# uszko.net
KiCad netlist of a schematic drawn in EAGLE
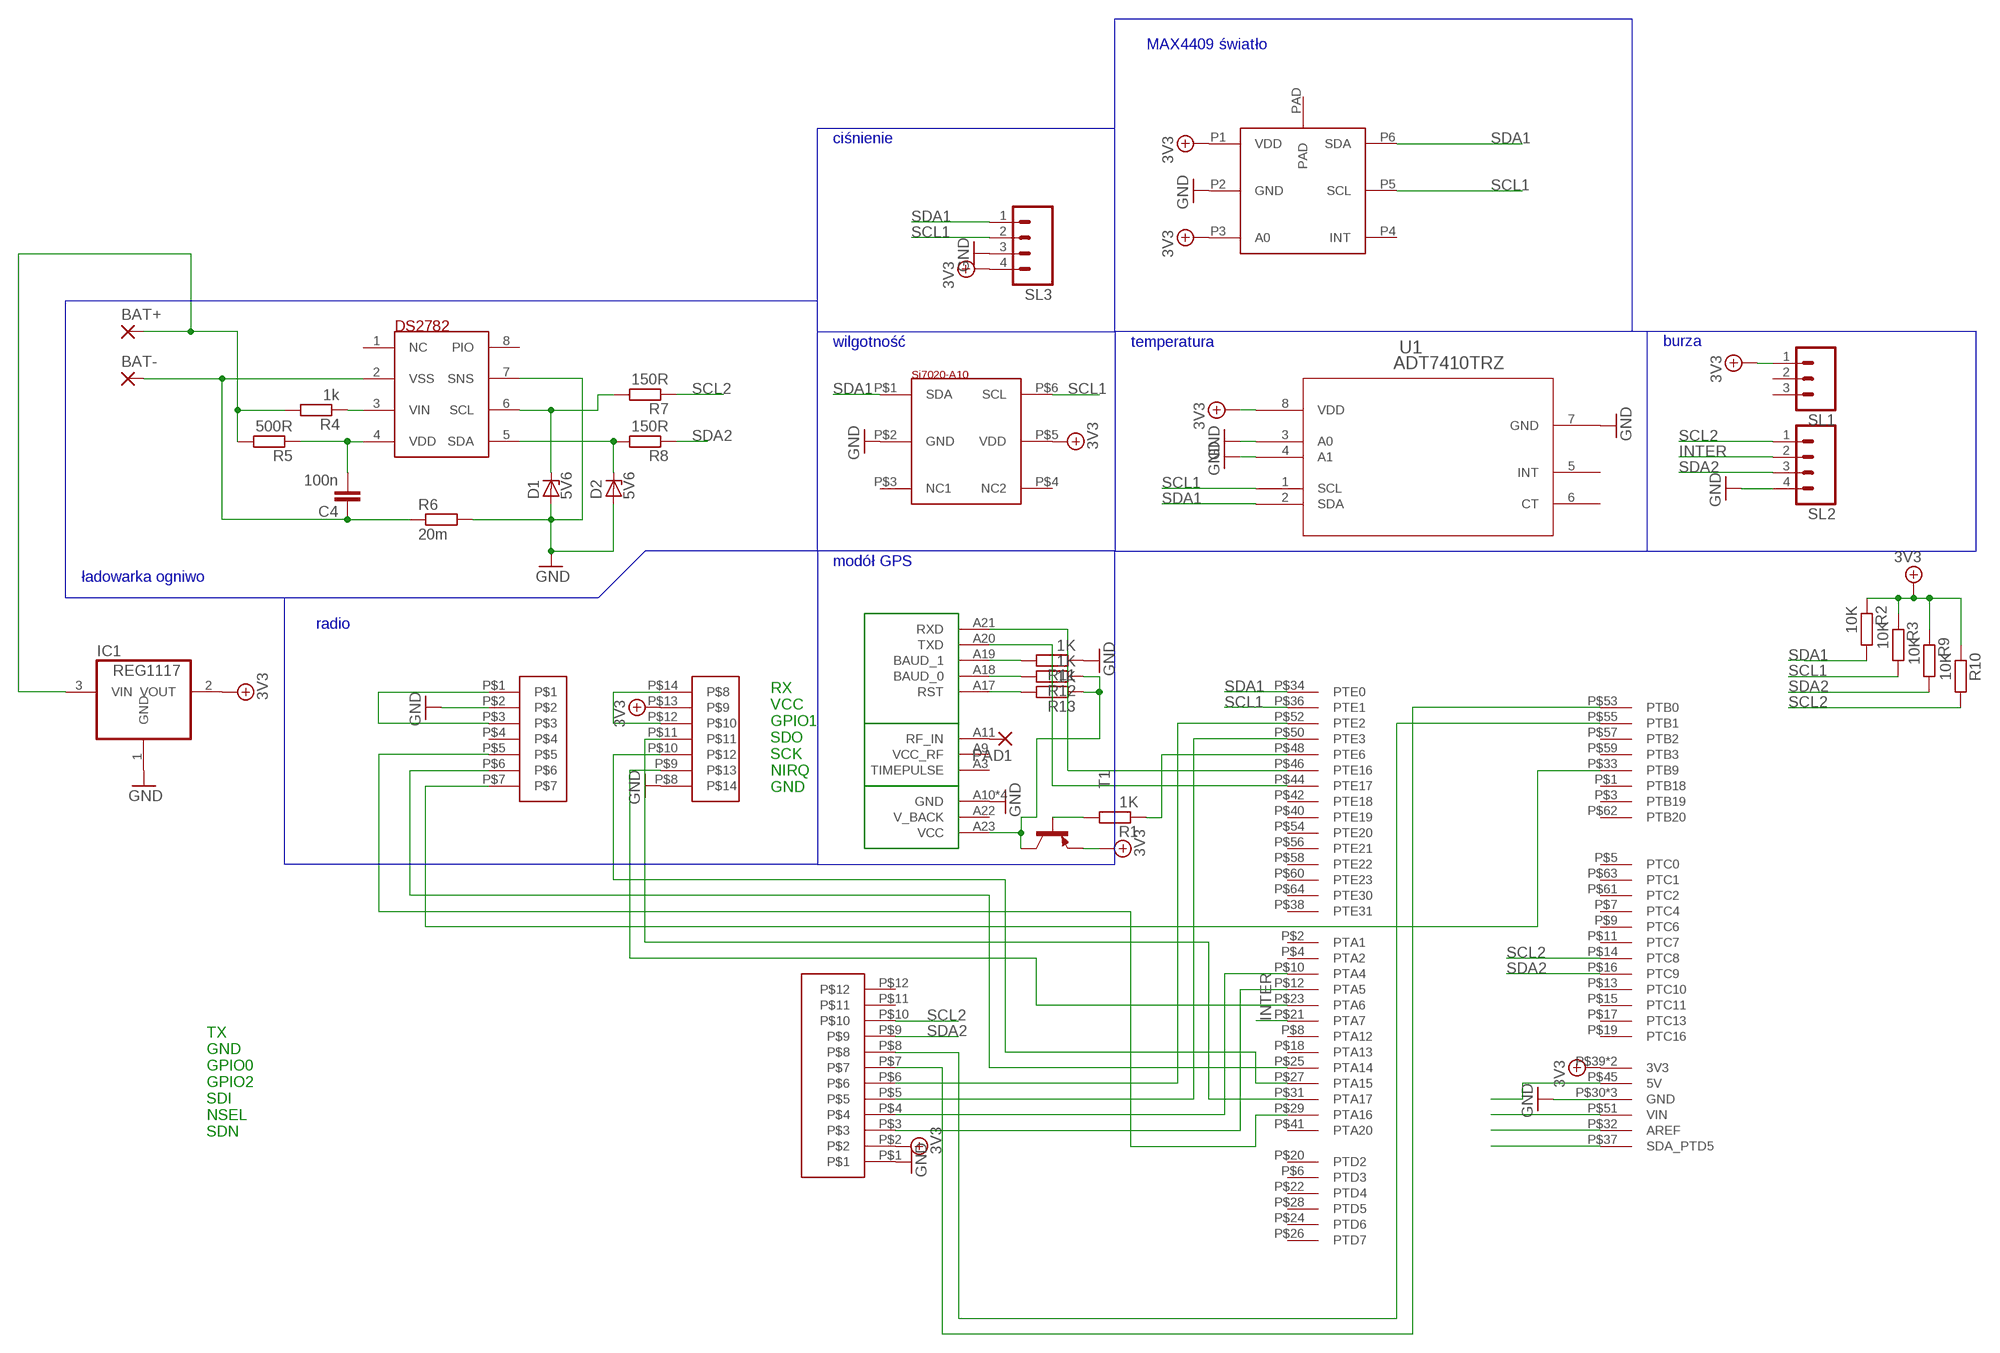
[diagram p0: schematic, sheet 1]

(export (version "E")
  (design (tool "Eeschema 10.0.6"))
  (components
    (comp (ref "BAT+")
      (value "2,54/0,8")
      (footprint "eagle-import:2,54_0,8")
      (libsource (lib "eagle-import") (part "2,54/0,8"))
    )
    (comp (ref "BAT-")
      (value "2,54/0,8")
      (footprint "eagle-import:2,54_0,8")
      (libsource (lib "eagle-import") (part "2,54/0,8"))
    )
    (comp (ref "C4")
      (value "100n")
      (footprint "eagle-import:C0805")
      (libsource (lib "eagle-import") (part "C-EUC0805"))
    )
    (comp (ref "D1")
      (value "5V6")
      (footprint "eagle-import:SOD80C")
      (libsource (lib "eagle-import") (part "ZENER-DIODESOD80C"))
    )
    (comp (ref "D2")
      (value "5V6")
      (footprint "eagle-import:SOD80C")
      (libsource (lib "eagle-import") (part "ZENER-DIODESOD80C"))
    )
    (comp (ref "IC1")
      (value "REG1117")
      (footprint "eagle-import:SOT223")
      (libsource (lib "eagle-import") (part "REG1117"))
    )
    (comp (ref "PAD1")
      (value "2,15/1,0")
      (footprint "eagle-import:2,15_1,0")
      (libsource (lib "eagle-import") (part "2,15/1,0"))
    )
    (comp (ref "R1")
      (value "1K")
      (footprint "eagle-import:M0805")
      (libsource (lib "eagle-import") (part "R-EU_M0805"))
    )
    (comp (ref "R2")
      (value "10K")
      (footprint "eagle-import:M0805")
      (libsource (lib "eagle-import") (part "R-EU_M0805"))
    )
    (comp (ref "R3")
      (value "10K")
      (footprint "eagle-import:M0805")
      (libsource (lib "eagle-import") (part "R-EU_M0805"))
    )
    (comp (ref "R4")
      (value "1k")
      (footprint "eagle-import:M0805")
      (libsource (lib "eagle-import") (part "R-EU_M0805"))
    )
    (comp (ref "R5")
      (value "500R")
      (footprint "eagle-import:M0805")
      (libsource (lib "eagle-import") (part "R-EU_M0805"))
    )
    (comp (ref "R6")
      (value "20m")
      (footprint "eagle-import:M1206")
      (libsource (lib "eagle-import") (part "R-EU_M1206"))
    )
    (comp (ref "R7")
      (value "150R")
      (footprint "eagle-import:M0805")
      (libsource (lib "eagle-import") (part "R-EU_M0805"))
    )
    (comp (ref "R8")
      (value "150R")
      (footprint "eagle-import:M0805")
      (libsource (lib "eagle-import") (part "R-EU_M0805"))
    )
    (comp (ref "R9")
      (value "10K")
      (footprint "eagle-import:M0805")
      (libsource (lib "eagle-import") (part "R-EU_M0805"))
    )
    (comp (ref "R10")
      (value "10K")
      (footprint "eagle-import:M0805")
      (libsource (lib "eagle-import") (part "R-EU_M0805"))
    )
    (comp (ref "R11")
      (value "1K")
      (footprint "eagle-import:M0805")
      (libsource (lib "eagle-import") (part "R-EU_M0805"))
    )
    (comp (ref "R12")
      (value "1K")
      (footprint "eagle-import:M0805")
      (libsource (lib "eagle-import") (part "R-EU_M0805"))
    )
    (comp (ref "R13")
      (value "1K")
      (footprint "eagle-import:M0805")
      (libsource (lib "eagle-import") (part "R-EU_M0805"))
    )
    (comp (ref "SL1")
      (value "M03")
      (footprint "eagle-import:03P")
      (libsource (lib "eagle-import") (part "M03"))
    )
    (comp (ref "SL2")
      (value "M04")
      (footprint "eagle-import:04P")
      (libsource (lib "eagle-import") (part "M04"))
    )
    (comp (ref "SL3")
      (value "M04")
      (footprint "eagle-import:04P")
      (fields (field (name "OC_FARNELL") "unknown") (field (name "OC_NEWARK") "unknown"))
      (libsource (lib "eagle-import") (part "M04"))
    )
    (comp (ref "T1")
      (value "-PNP-SOT23-BCE")
      (footprint "eagle-import:SOT23-BCE")
      (libsource (lib "eagle-import") (part "-PNP-SOT23-BCE"))
    )
    (comp (ref "U$1")
      (value "INTO_CON")
      (footprint "eagle-import:INTO_CON")
      (libsource (lib "eagle-import") (part "INTO_CON"))
    )
    (comp (ref "U$2")
      (value "GTS-4E-60")
      (footprint "eagle-import:GTS-4E-60")
      (libsource (lib "eagle-import") (part "GTS-4E-60"))
    )
    (comp (ref "U$3")
      (value "2X7PIN")
      (footprint "eagle-import:2X7PINCON")
      (libsource (lib "eagle-import") (part "2X7PIN"))
    )
    (comp (ref "U$4")
      (value "SI7020-A10")
      (footprint "eagle-import:DFN6(3X3MM)")
      (libsource (lib "eagle-import") (part "SI7020-A10"))
    )
    (comp (ref "U$5")
      (value "12PINCON")
      (footprint "eagle-import:12PIN2MMCON")
      (libsource (lib "eagle-import") (part "12PINCON"))
    )
    (comp (ref "U$6")
      (value "MAX44006")
      (footprint "eagle-import:6OTDFN")
      (libsource (lib "eagle-import") (part "MAX44006"))
    )
    (comp (ref "U$7")
      (value "DS2782")
      (footprint "eagle-import:TSSOP8")
      (libsource (lib "eagle-import") (part "DS2782"))
    )
    (comp (ref "U1")
      (value "ADT7410TRZ")
      (footprint "eagle-import:R_8")
      (libsource (lib "eagle-import") (part "ADT7410TRZ"))
    )
  )
  (nets
    (net (code "1") (name "/INTER") (class "Default")
      (node (ref "SL2") (pin "2") (pinfunction "2_2") (pintype "passive"))
      (node (ref "U$1") (pin "P$21") (pinfunction "PTA7_P$21") (pintype "bidirectional"))
    )
    (net (code "2") (name "/SCL1") (class "Default")
      (node (ref "R3") (pin "2") (pinfunction "2_2") (pintype "passive"))
      (node (ref "SL3") (pin "2") (pinfunction "2_2") (pintype "passive"))
      (node (ref "U$1") (pin "P$36") (pinfunction "PTE1_P$36") (pintype "bidirectional"))
      (node (ref "U$4") (pin "P$6") (pinfunction "SCL_P$6") (pintype "bidirectional"))
      (node (ref "U$6") (pin "P5") (pinfunction "SCL_P5") (pintype "bidirectional"))
      (node (ref "U1") (pin "1") (pinfunction "SCL_1") (pintype "passive"))
    )
    (net (code "3") (name "/SCL2") (class "Default")
      (node (ref "R10") (pin "2") (pinfunction "2_2") (pintype "passive"))
      (node (ref "R7") (pin "1") (pinfunction "1_1") (pintype "passive"))
      (node (ref "SL2") (pin "1") (pinfunction "1_1") (pintype "passive"))
      (node (ref "U$1") (pin "P$14") (pinfunction "PTC8_P$14") (pintype "bidirectional"))
      (node (ref "U$5") (pin "P$10") (pinfunction "P$10_P$10") (pintype "bidirectional"))
    )
    (net (code "4") (name "/SDA1") (class "Default")
      (node (ref "R2") (pin "2") (pinfunction "2_2") (pintype "passive"))
      (node (ref "SL3") (pin "1") (pinfunction "1_1") (pintype "passive"))
      (node (ref "U$1") (pin "P$34") (pinfunction "PTE0_P$34") (pintype "bidirectional"))
      (node (ref "U$4") (pin "P$1") (pinfunction "SDA_P$1") (pintype "bidirectional"))
      (node (ref "U$6") (pin "P6") (pinfunction "SDA_P6") (pintype "bidirectional"))
      (node (ref "U1") (pin "2") (pinfunction "SDA_2") (pintype "passive"))
    )
    (net (code "5") (name "/SDA2") (class "Default")
      (node (ref "R8") (pin "1") (pinfunction "1_1") (pintype "passive"))
      (node (ref "R9") (pin "2") (pinfunction "2_2") (pintype "passive"))
      (node (ref "SL2") (pin "3") (pinfunction "3_3") (pintype "passive"))
      (node (ref "U$1") (pin "P$16") (pinfunction "PTC9_P$16") (pintype "bidirectional"))
      (node (ref "U$5") (pin "P$9") (pinfunction "P$9_P$9") (pintype "bidirectional"))
    )
    (net (code "6") (name "3V3") (class "Default")
      (node (ref "IC1") (pin "2") (pinfunction "VOUT_2") (pintype "output"))
      (node (ref "R10") (pin "1") (pinfunction "1_1") (pintype "passive"))
      (node (ref "R2") (pin "1") (pinfunction "1_1") (pintype "passive"))
      (node (ref "R3") (pin "1") (pinfunction "1_1") (pintype "passive"))
      (node (ref "R9") (pin "1") (pinfunction "1_1") (pintype "passive"))
      (node (ref "SL1") (pin "1") (pinfunction "1_1") (pintype "passive"))
      (node (ref "SL3") (pin "4") (pinfunction "4_4") (pintype "passive"))
      (node (ref "T1") (pin "E") (pinfunction "E_E") (pintype "passive"))
      (node (ref "U$1") (pin "P$39") (pinfunction "3V3_P$39") (pintype "bidirectional"))
      (node (ref "U$1") (pin "P$43") (pinfunction "3V3_P$43") (pintype "bidirectional"))
      (node (ref "U$3") (pin "P$13") (pinfunction "P$9_P$13") (pintype "bidirectional"))
      (node (ref "U$4") (pin "P$5") (pinfunction "VDD_P$5") (pintype "bidirectional"))
      (node (ref "U$5") (pin "P$2") (pinfunction "P$2_P$2") (pintype "bidirectional"))
      (node (ref "U$6") (pin "P1") (pinfunction "VDD_P1") (pintype "bidirectional"))
      (node (ref "U$6") (pin "P3") (pinfunction "A0_P3") (pintype "bidirectional"))
      (node (ref "U1") (pin "8") (pinfunction "VDD_8") (pintype "passive"))
    )
    (net (code "7") (name "GND") (class "Default")
      (node (ref "D1") (pin "A") (pinfunction "A_A") (pintype "passive"))
      (node (ref "D2") (pin "A") (pinfunction "A_A") (pintype "passive"))
      (node (ref "IC1") (pin "1") (pinfunction "GND_1") (pintype "power_in"))
      (node (ref "R11") (pin "1") (pinfunction "1_1") (pintype "passive"))
      (node (ref "R6") (pin "2") (pinfunction "2_2") (pintype "passive"))
      (node (ref "SL2") (pin "4") (pinfunction "4_4") (pintype "passive"))
      (node (ref "SL3") (pin "3") (pinfunction "3_3") (pintype "passive"))
      (node (ref "U$1") (pin "P$30") (pinfunction "GND_P$30") (pintype "bidirectional"))
      (node (ref "U$1") (pin "P$47") (pinfunction "GND_P$47") (pintype "bidirectional"))
      (node (ref "U$1") (pin "P$49") (pinfunction "GND_P$49") (pintype "bidirectional"))
      (node (ref "U$2") (pin "A10") (pinfunction "GND_A10") (pintype "bidirectional"))
      (node (ref "U$2") (pin "A12") (pinfunction "GND_A12") (pintype "bidirectional"))
      (node (ref "U$2") (pin "A13") (pinfunction "GND_A13") (pintype "bidirectional"))
      (node (ref "U$2") (pin "A24") (pinfunction "GND_A24") (pintype "bidirectional"))
      (node (ref "U$3") (pin "P$2") (pinfunction "P$2_P$2") (pintype "bidirectional"))
      (node (ref "U$3") (pin "P$8") (pinfunction "P$14_P$8") (pintype "bidirectional"))
      (node (ref "U$4") (pin "P$2") (pinfunction "GND_P$2") (pintype "bidirectional"))
      (node (ref "U$5") (pin "P$1") (pinfunction "P$1_P$1") (pintype "bidirectional"))
      (node (ref "U$6") (pin "P2") (pinfunction "GND_P2") (pintype "bidirectional"))
      (node (ref "U$7") (pin "7") (pinfunction "SNS_7") (pintype "bidirectional"))
      (node (ref "U1") (pin "3") (pinfunction "A0_3") (pintype "passive"))
      (node (ref "U1") (pin "4") (pinfunction "A1_4") (pintype "passive"))
      (node (ref "U1") (pin "7") (pinfunction "GND_7") (pintype "passive"))
    )
    (net (code "8") (name "Net-(BAT+-P)") (class "Default")
      (node (ref "BAT+") (pin "1") (pinfunction "P_1") (pintype "passive"))
      (node (ref "IC1") (pin "3") (pinfunction "VIN_3") (pintype "input"))
      (node (ref "R4") (pin "2") (pinfunction "2_2") (pintype "passive"))
      (node (ref "R5") (pin "2") (pinfunction "2_2") (pintype "passive"))
    )
    (net (code "9") (name "Net-(BAT--P)") (class "Default")
      (node (ref "BAT-") (pin "1") (pinfunction "P_1") (pintype "passive"))
      (node (ref "C4") (pin "1") (pinfunction "1_1") (pintype "passive"))
      (node (ref "R6") (pin "1") (pinfunction "1_1") (pintype "passive"))
      (node (ref "U$7") (pin "2") (pinfunction "VSS_2") (pintype "bidirectional"))
    )
    (net (code "10") (name "Net-(PAD1-P)") (class "Default")
      (node (ref "PAD1") (pin "1") (pinfunction "P_1") (pintype "passive"))
      (node (ref "U$2") (pin "A11") (pinfunction "RF_IN_A11") (pintype "bidirectional"))
    )
    (net (code "11") (name "Net-(R1-Pad2)") (class "Default")
      (node (ref "R1") (pin "2") (pinfunction "2_2") (pintype "passive"))
      (node (ref "T1") (pin "B") (pinfunction "B_B") (pintype "passive"))
    )
    (net (code "12") (name "Net-(U$1-PTA4)") (class "Default")
      (node (ref "U$1") (pin "P$10") (pinfunction "PTA4_P$10") (pintype "bidirectional"))
      (node (ref "U$5") (pin "P$4") (pinfunction "P$4_P$4") (pintype "bidirectional"))
    )
    (net (code "13") (name "Net-(U$1-PTA5)") (class "Default")
      (node (ref "U$1") (pin "P$12") (pinfunction "PTA5_P$12") (pintype "bidirectional"))
      (node (ref "U$5") (pin "P$3") (pinfunction "P$3_P$3") (pintype "bidirectional"))
    )
    (net (code "14") (name "Net-(U$1-PTA6)") (class "Default")
      (node (ref "U$1") (pin "P$23") (pinfunction "PTA6_P$23") (pintype "bidirectional"))
      (node (ref "U$3") (pin "P$9") (pinfunction "P$13_P$9") (pintype "bidirectional"))
    )
    (net (code "15") (name "Net-(U$1-PTA14)") (class "Default")
      (node (ref "U$1") (pin "P$25") (pinfunction "PTA14_P$25") (pintype "bidirectional"))
      (node (ref "U$3") (pin "P$6") (pinfunction "P$6_P$6") (pintype "bidirectional"))
    )
    (net (code "16") (name "Net-(U$1-PTA15)") (class "Default")
      (node (ref "U$1") (pin "P$27") (pinfunction "PTA15_P$27") (pintype "bidirectional"))
      (node (ref "U$3") (pin "P$10") (pinfunction "P$12_P$10") (pintype "bidirectional"))
    )
    (net (code "17") (name "Net-(U$1-PTA16)") (class "Default")
      (node (ref "U$1") (pin "P$29") (pinfunction "PTA16_P$29") (pintype "bidirectional"))
      (node (ref "U$3") (pin "P$5") (pinfunction "P$5_P$5") (pintype "bidirectional"))
    )
    (net (code "18") (name "Net-(U$1-PTA17)") (class "Default")
      (node (ref "U$1") (pin "P$31") (pinfunction "PTA17_P$31") (pintype "bidirectional"))
      (node (ref "U$3") (pin "P$11") (pinfunction "P$11_P$11") (pintype "bidirectional"))
    )
    (net (code "19") (name "Net-(U$1-PTB0)") (class "Default")
      (node (ref "U$1") (pin "P$53") (pinfunction "PTB0_P$53") (pintype "bidirectional"))
      (node (ref "U$5") (pin "P$7") (pinfunction "P$7_P$7") (pintype "bidirectional"))
    )
    (net (code "20") (name "Net-(U$1-PTB1)") (class "Default")
      (node (ref "U$1") (pin "P$55") (pinfunction "PTB1_P$55") (pintype "bidirectional"))
      (node (ref "U$5") (pin "P$8") (pinfunction "P$8_P$8") (pintype "bidirectional"))
    )
    (net (code "21") (name "Net-(U$1-PTB9)") (class "Default")
      (node (ref "U$1") (pin "P$33") (pinfunction "PTB9_P$33") (pintype "bidirectional"))
      (node (ref "U$3") (pin "P$7") (pinfunction "P$7_P$7") (pintype "bidirectional"))
    )
    (net (code "22") (name "Net-(U$1-PTE2)") (class "Default")
      (node (ref "U$1") (pin "P$52") (pinfunction "PTE2_P$52") (pintype "bidirectional"))
      (node (ref "U$5") (pin "P$6") (pinfunction "P$6_P$6") (pintype "bidirectional"))
    )
    (net (code "23") (name "Net-(U$1-PTE3)") (class "Default")
      (node (ref "U$1") (pin "P$50") (pinfunction "PTE3_P$50") (pintype "bidirectional"))
      (node (ref "U$5") (pin "P$5") (pinfunction "P$5_P$5") (pintype "bidirectional"))
    )
    (net (code "24") (name "Net-(U$1-PTE6)") (class "Default")
      (node (ref "R1") (pin "1") (pinfunction "1_1") (pintype "passive"))
      (node (ref "U$1") (pin "P$48") (pinfunction "PTE6_P$48") (pintype "bidirectional"))
    )
    (net (code "25") (name "Net-(U$1-PTE16)") (class "Default")
      (node (ref "U$1") (pin "P$46") (pinfunction "PTE16_P$46") (pintype "bidirectional"))
      (node (ref "U$2") (pin "A21") (pinfunction "RXD_A21") (pintype "bidirectional"))
    )
    (net (code "26") (name "Net-(U$1-PTE17)") (class "Default")
      (node (ref "U$1") (pin "P$44") (pinfunction "PTE17_P$44") (pintype "bidirectional"))
      (node (ref "U$2") (pin "A20") (pinfunction "TXD_A20") (pintype "bidirectional"))
    )
    (net (code "27") (name "Net-(U$2-BAUD_0)") (class "Default")
      (node (ref "R12") (pin "2") (pinfunction "2_2") (pintype "passive"))
      (node (ref "U$2") (pin "A18") (pinfunction "BAUD_0_A18") (pintype "bidirectional"))
    )
    (net (code "28") (name "Net-(U$2-BAUD_1)") (class "Default")
      (node (ref "R11") (pin "2") (pinfunction "2_2") (pintype "passive"))
      (node (ref "U$2") (pin "A19") (pinfunction "BAUD_1_A19") (pintype "bidirectional"))
    )
    (net (code "29") (name "Net-(U$2-RST)") (class "Default")
      (node (ref "R13") (pin "2") (pinfunction "2_2") (pintype "passive"))
      (node (ref "U$2") (pin "A17") (pinfunction "RST_A17") (pintype "bidirectional"))
    )
    (net (code "30") (name "Net-(U$2-VCC)") (class "Default")
      (node (ref "R12") (pin "1") (pinfunction "1_1") (pintype "passive"))
      (node (ref "R13") (pin "1") (pinfunction "1_1") (pintype "passive"))
      (node (ref "T1") (pin "C") (pinfunction "C_C") (pintype "passive"))
      (node (ref "U$2") (pin "A23") (pinfunction "VCC_A23") (pintype "bidirectional"))
    )
    (net (code "31") (name "Net-(U$3-P$10)") (class "Default")
      (node (ref "U$3") (pin "P$12") (pinfunction "P$10_P$12") (pintype "bidirectional"))
      (node (ref "U$3") (pin "P$14") (pinfunction "P$8_P$14") (pintype "bidirectional"))
    )
    (net (code "32") (name "Net-(U$3-PadP$1)") (class "Default")
      (node (ref "U$3") (pin "P$1") (pinfunction "P$1_P$1") (pintype "bidirectional"))
      (node (ref "U$3") (pin "P$3") (pinfunction "P$3_P$3") (pintype "bidirectional"))
    )
    (net (code "33") (name "Net-(U$7-SCL)") (class "Default")
      (node (ref "D1") (pin "C") (pinfunction "C_C") (pintype "passive"))
      (node (ref "R7") (pin "2") (pinfunction "2_2") (pintype "passive"))
      (node (ref "U$7") (pin "6") (pinfunction "SCL_6") (pintype "bidirectional"))
    )
    (net (code "34") (name "Net-(U$7-SDA)") (class "Default")
      (node (ref "D2") (pin "C") (pinfunction "C_C") (pintype "passive"))
      (node (ref "R8") (pin "2") (pinfunction "2_2") (pintype "passive"))
      (node (ref "U$7") (pin "5") (pinfunction "SDA_5") (pintype "bidirectional"))
    )
    (net (code "35") (name "Net-(U$7-VDD)") (class "Default")
      (node (ref "C4") (pin "2") (pinfunction "2_2") (pintype "passive"))
      (node (ref "R5") (pin "1") (pinfunction "1_1") (pintype "passive"))
      (node (ref "U$7") (pin "4") (pinfunction "VDD_4") (pintype "bidirectional"))
    )
    (net (code "36") (name "Net-(U$7-VIN)") (class "Default")
      (node (ref "R4") (pin "1") (pinfunction "1_1") (pintype "passive"))
      (node (ref "U$7") (pin "3") (pinfunction "VIN_3") (pintype "bidirectional"))
    )
    (net (code "37") (name "unconnected-(SL1-Pad2)") (class "Default")
      (node (ref "SL1") (pin "2") (pinfunction "2_2") (pintype "passive"))
    )
    (net (code "38") (name "unconnected-(SL1-Pad3)") (class "Default")
      (node (ref "SL1") (pin "3") (pinfunction "3_3") (pintype "passive"))
    )
    (net (code "39") (name "unconnected-(U$1-5V-PadP$45)") (class "Default")
      (node (ref "U$1") (pin "P$45") (pinfunction "5V_P$45") (pintype "bidirectional"))
    )
    (net (code "40") (name "unconnected-(U$1-AREF-PadP$32)") (class "Default")
      (node (ref "U$1") (pin "P$32") (pinfunction "AREF_P$32") (pintype "bidirectional"))
    )
    (net (code "41") (name "unconnected-(U$1-PTA1-PadP$2)") (class "Default")
      (node (ref "U$1") (pin "P$2") (pinfunction "PTA1_P$2") (pintype "bidirectional"))
    )
    (net (code "42") (name "unconnected-(U$1-PTA2-PadP$4)") (class "Default")
      (node (ref "U$1") (pin "P$4") (pinfunction "PTA2_P$4") (pintype "bidirectional"))
    )
    (net (code "43") (name "unconnected-(U$1-PTA12-PadP$8)") (class "Default")
      (node (ref "U$1") (pin "P$8") (pinfunction "PTA12_P$8") (pintype "bidirectional"))
    )
    (net (code "44") (name "unconnected-(U$1-PTA13-PadP$18)") (class "Default")
      (node (ref "U$1") (pin "P$18") (pinfunction "PTA13_P$18") (pintype "bidirectional"))
    )
    (net (code "45") (name "unconnected-(U$1-PTA20-PadP$41)") (class "Default")
      (node (ref "U$1") (pin "P$41") (pinfunction "PTA20_P$41") (pintype "bidirectional"))
    )
    (net (code "46") (name "unconnected-(U$1-PTB2-PadP$57)") (class "Default")
      (node (ref "U$1") (pin "P$57") (pinfunction "PTB2_P$57") (pintype "bidirectional"))
    )
    (net (code "47") (name "unconnected-(U$1-PTB3-PadP$59)") (class "Default")
      (node (ref "U$1") (pin "P$59") (pinfunction "PTB3_P$59") (pintype "bidirectional"))
    )
    (net (code "48") (name "unconnected-(U$1-PTB18-PadP$1)") (class "Default")
      (node (ref "U$1") (pin "P$1") (pinfunction "PTB18_P$1") (pintype "bidirectional"))
    )
    (net (code "49") (name "unconnected-(U$1-PTB19-PadP$3)") (class "Default")
      (node (ref "U$1") (pin "P$3") (pinfunction "PTB19_P$3") (pintype "bidirectional"))
    )
    (net (code "50") (name "unconnected-(U$1-PTB20-PadP$62)") (class "Default")
      (node (ref "U$1") (pin "P$62") (pinfunction "PTB20_P$62") (pintype "bidirectional"))
    )
    (net (code "51") (name "unconnected-(U$1-PTC0-PadP$5)") (class "Default")
      (node (ref "U$1") (pin "P$5") (pinfunction "PTC0_P$5") (pintype "bidirectional"))
    )
    (net (code "52") (name "unconnected-(U$1-PTC1-PadP$63)") (class "Default")
      (node (ref "U$1") (pin "P$63") (pinfunction "PTC1_P$63") (pintype "bidirectional"))
    )
    (net (code "53") (name "unconnected-(U$1-PTC2-PadP$61)") (class "Default")
      (node (ref "U$1") (pin "P$61") (pinfunction "PTC2_P$61") (pintype "bidirectional"))
    )
    (net (code "54") (name "unconnected-(U$1-PTC4-PadP$7)") (class "Default")
      (node (ref "U$1") (pin "P$7") (pinfunction "PTC4_P$7") (pintype "bidirectional"))
    )
    (net (code "55") (name "unconnected-(U$1-PTC6-PadP$9)") (class "Default")
      (node (ref "U$1") (pin "P$9") (pinfunction "PTC6_P$9") (pintype "bidirectional"))
    )
    (net (code "56") (name "unconnected-(U$1-PTC7-PadP$11)") (class "Default")
      (node (ref "U$1") (pin "P$11") (pinfunction "PTC7_P$11") (pintype "bidirectional"))
    )
    (net (code "57") (name "unconnected-(U$1-PTC10-PadP$13)") (class "Default")
      (node (ref "U$1") (pin "P$13") (pinfunction "PTC10_P$13") (pintype "bidirectional"))
    )
    (net (code "58") (name "unconnected-(U$1-PTC11-PadP$15)") (class "Default")
      (node (ref "U$1") (pin "P$15") (pinfunction "PTC11_P$15") (pintype "bidirectional"))
    )
    (net (code "59") (name "unconnected-(U$1-PTC13-PadP$17)") (class "Default")
      (node (ref "U$1") (pin "P$17") (pinfunction "PTC13_P$17") (pintype "bidirectional"))
    )
    (net (code "60") (name "unconnected-(U$1-PTC16-PadP$19)") (class "Default")
      (node (ref "U$1") (pin "P$19") (pinfunction "PTC16_P$19") (pintype "bidirectional"))
    )
    (net (code "61") (name "unconnected-(U$1-PTD2-PadP$20)") (class "Default")
      (node (ref "U$1") (pin "P$20") (pinfunction "PTD2_P$20") (pintype "bidirectional"))
    )
    (net (code "62") (name "unconnected-(U$1-PTD3-PadP$6)") (class "Default")
      (node (ref "U$1") (pin "P$6") (pinfunction "PTD3_P$6") (pintype "bidirectional"))
    )
    (net (code "63") (name "unconnected-(U$1-PTD4-PadP$22)") (class "Default")
      (node (ref "U$1") (pin "P$22") (pinfunction "PTD4_P$22") (pintype "bidirectional"))
    )
    (net (code "64") (name "unconnected-(U$1-PTD5-PadP$28)") (class "Default")
      (node (ref "U$1") (pin "P$28") (pinfunction "PTD5_P$28") (pintype "bidirectional"))
    )
    (net (code "65") (name "unconnected-(U$1-PTD6-PadP$24)") (class "Default")
      (node (ref "U$1") (pin "P$24") (pinfunction "PTD6_P$24") (pintype "bidirectional"))
    )
    (net (code "66") (name "unconnected-(U$1-PTD7-PadP$26)") (class "Default")
      (node (ref "U$1") (pin "P$26") (pinfunction "PTD7_P$26") (pintype "bidirectional"))
    )
    (net (code "67") (name "unconnected-(U$1-PTE18-PadP$42)") (class "Default")
      (node (ref "U$1") (pin "P$42") (pinfunction "PTE18_P$42") (pintype "bidirectional"))
    )
    (net (code "68") (name "unconnected-(U$1-PTE19-PadP$40)") (class "Default")
      (node (ref "U$1") (pin "P$40") (pinfunction "PTE19_P$40") (pintype "bidirectional"))
    )
    (net (code "69") (name "unconnected-(U$1-PTE20-PadP$54)") (class "Default")
      (node (ref "U$1") (pin "P$54") (pinfunction "PTE20_P$54") (pintype "bidirectional"))
    )
    (net (code "70") (name "unconnected-(U$1-PTE21-PadP$56)") (class "Default")
      (node (ref "U$1") (pin "P$56") (pinfunction "PTE21_P$56") (pintype "bidirectional"))
    )
    (net (code "71") (name "unconnected-(U$1-PTE22-PadP$58)") (class "Default")
      (node (ref "U$1") (pin "P$58") (pinfunction "PTE22_P$58") (pintype "bidirectional"))
    )
    (net (code "72") (name "unconnected-(U$1-PTE23-PadP$60)") (class "Default")
      (node (ref "U$1") (pin "P$60") (pinfunction "PTE23_P$60") (pintype "bidirectional"))
    )
    (net (code "73") (name "unconnected-(U$1-PTE30-PadP$64)") (class "Default")
      (node (ref "U$1") (pin "P$64") (pinfunction "PTE30_P$64") (pintype "bidirectional"))
    )
    (net (code "74") (name "unconnected-(U$1-PTE31-PadP$38)") (class "Default")
      (node (ref "U$1") (pin "P$38") (pinfunction "PTE31_P$38") (pintype "bidirectional"))
    )
    (net (code "75") (name "unconnected-(U$1-SDA_PTD5-PadP$37)") (class "Default")
      (node (ref "U$1") (pin "P$37") (pinfunction "SDA_PTD5_P$37") (pintype "bidirectional"))
    )
    (net (code "76") (name "unconnected-(U$1-VIN-PadP$51)") (class "Default")
      (node (ref "U$1") (pin "P$51") (pinfunction "VIN_P$51") (pintype "bidirectional"))
    )
    (net (code "77") (name "unconnected-(U$2-TIMEPULSE-PadA3)") (class "Default")
      (node (ref "U$2") (pin "A3") (pinfunction "TIMEPULSE_A3") (pintype "bidirectional"))
    )
    (net (code "78") (name "unconnected-(U$2-VCC_RF-PadA9)") (class "Default")
      (node (ref "U$2") (pin "A9") (pinfunction "VCC_RF_A9") (pintype "bidirectional"))
    )
    (net (code "79") (name "unconnected-(U$2-V_BACK-PadA22)") (class "Default")
      (node (ref "U$2") (pin "A22") (pinfunction "V_BACK_A22") (pintype "bidirectional"))
    )
    (net (code "80") (name "unconnected-(U$3-PadP$4)") (class "Default")
      (node (ref "U$3") (pin "P$4") (pinfunction "P$4_P$4") (pintype "bidirectional"))
    )
    (net (code "81") (name "unconnected-(U$4-NC1-PadP$3)") (class "Default")
      (node (ref "U$4") (pin "P$3") (pinfunction "NC1_P$3") (pintype "bidirectional"))
    )
    (net (code "82") (name "unconnected-(U$4-NC2-PadP$4)") (class "Default")
      (node (ref "U$4") (pin "P$4") (pinfunction "NC2_P$4") (pintype "bidirectional"))
    )
    (net (code "83") (name "unconnected-(U$5-PadP$11)") (class "Default")
      (node (ref "U$5") (pin "P$11") (pinfunction "P$11_P$11") (pintype "bidirectional"))
    )
    (net (code "84") (name "unconnected-(U$5-PadP$12)") (class "Default")
      (node (ref "U$5") (pin "P$12") (pinfunction "P$12_P$12") (pintype "bidirectional"))
    )
    (net (code "85") (name "unconnected-(U$6-INT-PadP4)") (class "Default")
      (node (ref "U$6") (pin "P4") (pinfunction "INT_P4") (pintype "bidirectional"))
    )
    (net (code "86") (name "unconnected-(U$6-PadPAD)") (class "Default")
      (node (ref "U$6") (pin "PAD") (pinfunction "PAD_PAD") (pintype "bidirectional"))
    )
    (net (code "87") (name "unconnected-(U$7-NC-Pad1)") (class "Default")
      (node (ref "U$7") (pin "1") (pinfunction "NC_1") (pintype "bidirectional"))
    )
    (net (code "88") (name "unconnected-(U$7-PIO-Pad8)") (class "Default")
      (node (ref "U$7") (pin "8") (pinfunction "PIO_8") (pintype "bidirectional"))
    )
    (net (code "89") (name "unconnected-(U1-CT-Pad6)") (class "Default")
      (node (ref "U1") (pin "6") (pinfunction "CT_6") (pintype "passive"))
    )
    (net (code "90") (name "unconnected-(U1-INT-Pad5)") (class "Default")
      (node (ref "U1") (pin "5") (pinfunction "INT_5") (pintype "passive"))
    )
  )
)
